# POWER.net
KiCad netlist of a schematic drawn in Altium Designer
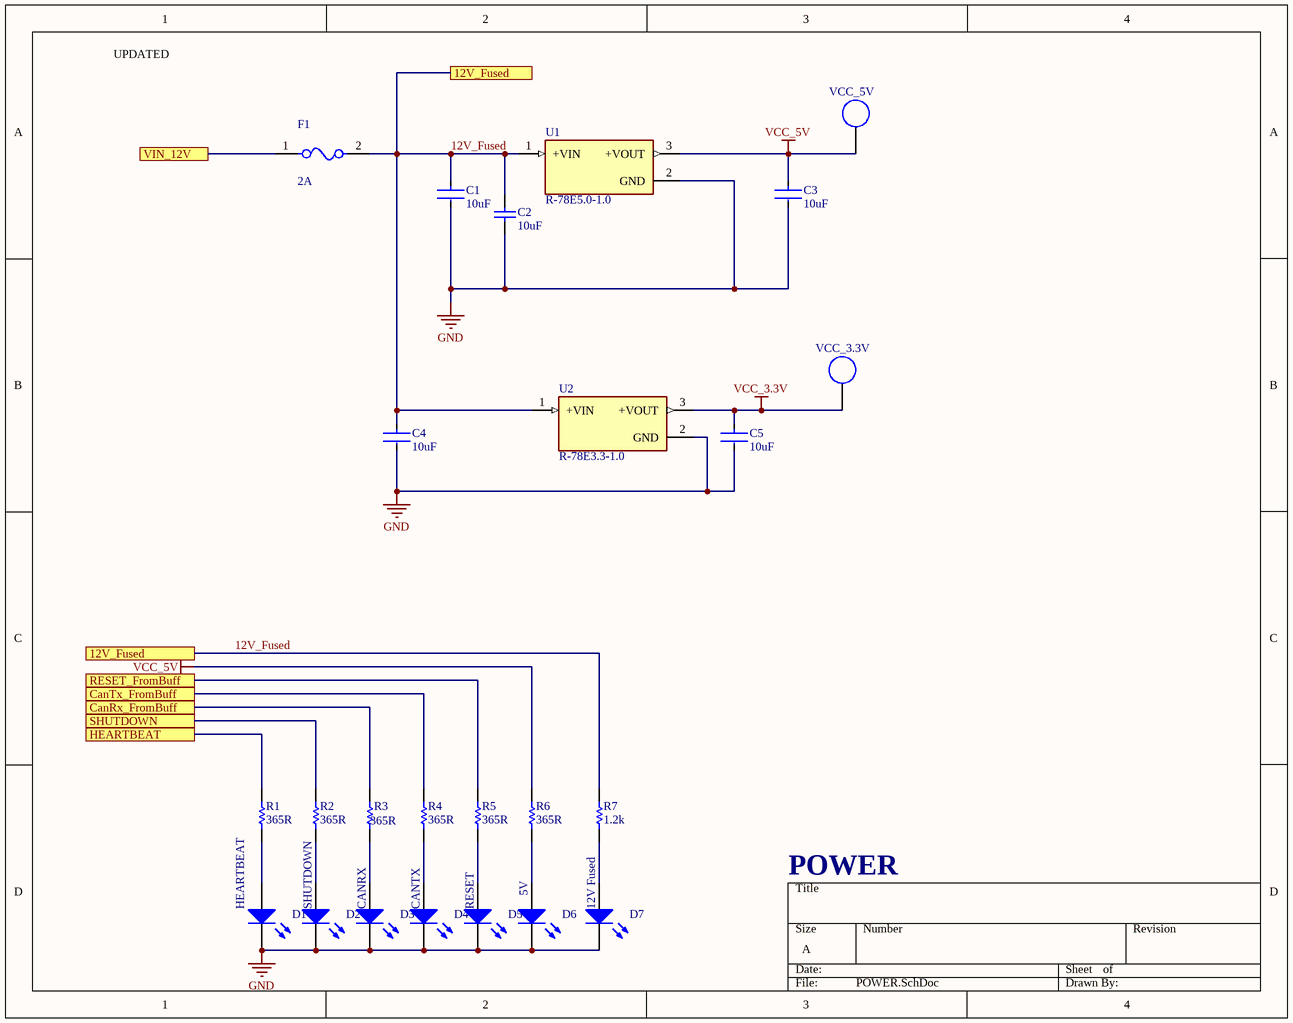
[diagram p0: POWER.SchDoc]

(export (version "E")
  (design (tool "Eeschema 10.0.6"))
  (components
    (comp (ref "C1")
      (value "10uF")
      (footprint "FP-C2012-125-0_2-MFG")
      (description "Multilayer Ceramic Capacitors 10μF ±10% 16V X6S SMD 0805")
      (fields (field (name "TOLERANCE") "10%"))
      (libsource (lib "Altium Content Vault") (part "b4654b650e69147ec39a6b967a45e02"))
    )
    (comp (ref "C2")
      (value "10uF")
      (footprint "CAPPRD200W50D550H1250")
      (description "Cap Alum 10UF 20% 25V Radial")
      (fields (field (name "PUBLISHER") "T.Tallo"))
      (libsource (lib "Passives") (part "Cap, TH, Electrolytic_5mm"))
    )
    (comp (ref "C3")
      (value "10uF")
      (footprint "FP-C2012-125-0_2-MFG")
      (description "Multilayer Ceramic Capacitors 10μF ±10% 16V X6S SMD 0805")
      (fields (field (name "TOLERANCE") "10%"))
      (libsource (lib "Altium Content Vault") (part "b4654b650e69147ec39a6b967a45e02"))
    )
    (comp (ref "C4")
      (value "10uF")
      (footprint "FP-C2012-125-0_2-MFG")
      (description "Multilayer Ceramic Capacitors 10μF ±10% 16V X6S SMD 0805")
      (fields (field (name "TOLERANCE") "10%"))
      (libsource (lib "Altium Content Vault") (part "b4654b650e69147ec39a6b967a45e02"))
    )
    (comp (ref "C5")
      (value "10uF")
      (footprint "FP-C2012-125-0_2-MFG")
      (description "Multilayer Ceramic Capacitors 10μF ±10% 16V X6S SMD 0805")
      (fields (field (name "TOLERANCE") "10%"))
      (libsource (lib "Altium Content Vault") (part "b4654b650e69147ec39a6b967a45e02"))
    )
    (comp (ref "D1")
      (value "HEARTBEAT")
      (footprint "0805_A")
      (description "SMD mono-color Chip LED, WL-SMCW, Bright Green")
      (fields (field (name "PARTNUMBER") "150080VS75000") (field (name "MANUFACTURER") "Wuerth Elektronik"))
      (libsource (lib "Altium Content Vault") (part "WE-LED_K1A2-2"))
    )
    (comp (ref "D2")
      (value "SHUTDOWN")
      (footprint "0805_A")
      (description "SMD mono-color Chip LED, WL-SMCW, Bright Green")
      (fields (field (name "PARTNUMBER") "150080VS75000") (field (name "MANUFACTURER") "Wuerth Elektronik"))
      (libsource (lib "Altium Content Vault") (part "WE-LED_K1A2-2"))
    )
    (comp (ref "D3")
      (value "CANRX")
      (footprint "0805_A")
      (description "SMD mono-color Chip LED, WL-SMCW, Bright Green")
      (fields (field (name "PARTNUMBER") "150080VS75000") (field (name "MANUFACTURER") "Wuerth Elektronik"))
      (libsource (lib "Altium Content Vault") (part "WE-LED_K1A2-2"))
    )
    (comp (ref "D4")
      (value "CANTX")
      (footprint "0805_A")
      (description "SMD mono-color Chip LED, WL-SMCW, Bright Green")
      (fields (field (name "PARTNUMBER") "150080VS75000") (field (name "MANUFACTURER") "Wuerth Elektronik"))
      (libsource (lib "Altium Content Vault") (part "WE-LED_K1A2-2"))
    )
    (comp (ref "D5")
      (value "RESET")
      (footprint "0805_A")
      (description "SMD mono-color Chip LED, WL-SMCW, Bright Green")
      (fields (field (name "PARTNUMBER") "150080VS75000") (field (name "MANUFACTURER") "Wuerth Elektronik"))
      (libsource (lib "Altium Content Vault") (part "WE-LED_K1A2-2"))
    )
    (comp (ref "D6")
      (value "5V")
      (footprint "0805_A")
      (description "SMD mono-color Chip LED, WL-SMCW, Bright Green")
      (fields (field (name "PARTNUMBER") "150080VS75000") (field (name "MANUFACTURER") "Wuerth Elektronik"))
      (libsource (lib "Altium Content Vault") (part "WE-LED_K1A2-2"))
    )
    (comp (ref "D7")
      (value "12V Fused")
      (footprint "0805_A")
      (description "SMD mono-color Chip LED, WL-SMCW, Bright Green")
      (fields (field (name "PARTNUMBER") "150080VS75000") (field (name "MANUFACTURER") "Wuerth Elektronik"))
      (libsource (lib "Altium Content Vault") (part "WE-LED_K1A2-2"))
    )
    (comp (ref "F1")
      (value "2A")
      (footprint "FP-0154-MFG")
      (description "FUSE BOARD MNT 2A 125VAC/VDC SMD")
      (fields
        (field (name "OCTOPART") "https://octopart.com/0154002.dr-littelfuse-565858")
        (field (name "MANUFACTURER PART NUMBER") "0154002.DR")
      )
      (libsource (lib "Altium Content Vault") (part "5bcf9b9f640e542cf0359d10258e979"))
    )
    (comp (ref "R1")
      (value "365R")
      (footprint "RESC2013X60X35ML10T20")
      (fields (field (name "PART NUMBER") "RC0805FR-07365RL") (field (name "MANUFACTURER") "Yageo"))
      (libsource (lib "Altium Content Vault") (part "RES"))
    )
    (comp (ref "R2")
      (value "365R")
      (footprint "RESC2013X60X35ML10T20")
      (fields (field (name "PART NUMBER") "RC0805FR-07365RL") (field (name "MANUFACTURER") "Yageo"))
      (libsource (lib "Altium Content Vault") (part "RES"))
    )
    (comp (ref "R3")
      (value "365R")
      (footprint "RESC2013X60X35ML10T20")
      (fields (field (name "PART NUMBER") "RC0805FR-07365RL") (field (name "MANUFACTURER") "Yageo"))
      (libsource (lib "Altium Content Vault") (part "RES"))
    )
    (comp (ref "R4")
      (value "365R")
      (footprint "RESC2013X60X35ML10T20")
      (fields (field (name "PART NUMBER") "RC0805FR-07365RL") (field (name "MANUFACTURER") "Yageo"))
      (libsource (lib "Altium Content Vault") (part "RES"))
    )
    (comp (ref "R5")
      (value "365R")
      (footprint "RESC2013X60X35ML10T20")
      (fields (field (name "PART NUMBER") "RC0805FR-07365RL") (field (name "MANUFACTURER") "Yageo"))
      (libsource (lib "Altium Content Vault") (part "RES"))
    )
    (comp (ref "R6")
      (value "365R")
      (footprint "RESC2013X60X35ML10T20")
      (fields (field (name "PART NUMBER") "RC0805FR-07365RL") (field (name "MANUFACTURER") "Yageo"))
      (libsource (lib "Altium Content Vault") (part "RES"))
    )
    (comp (ref "R7")
      (value "1.2k")
      (footprint "RESC2013X60X35ML10T20")
      (fields (field (name "PART NUMBER") "RC0805FR-071K24L") (field (name "MANUFACTURER") "Yageo"))
      (libsource (lib "Altium Content Vault") (part "RES"))
    )
    (comp (ref "U1")
      (value "R-78E5.0-1.0")
      (footprint "CONV_R-78E5.0-1.0")
      (description "1A DC/DC-Converter 'INNOLINE' SIP3 reg")
      (fields (field (name "MF") "Recom Power"))
      (libsource (lib "BMS_MasterboardUpdated_1") (part "R-78E5.0-1.0"))
    )
    (comp (ref "U2")
      (value "R-78E3.3-1.0")
      (footprint "CONV_R-78E3.3-1.0")
      (description "1A DC/DC-Converter 'INNOLINE' SIP3 reg")
      (fields (field (name "MF") "Recom Power") (field (name "DIGI-KEY_PART_NUMBER") "945-2409-5-ND"))
      (libsource (lib "BMS_MasterboardUpdated_1") (part "R-78E3.3-1.0"))
    )
    (comp (ref "VCC_3.3V")
      (value "5015")
      (footprint "5015")
      (description "SMD Test Point")
      (fields (field (name "MANUFACTURER") "Keystone Electronics") (field (name "PUBLISHER") "T.Tallo"))
      (libsource (lib "Connectors") (part "5015"))
    )
    (comp (ref "VCC_5V")
      (value "5015")
      (footprint "5015")
      (description "SMD Test Point")
      (fields (field (name "MANUFACTURER") "Keystone Electronics") (field (name "PUBLISHER") "T.Tallo"))
      (libsource (lib "Connectors") (part "5015"))
    )
  )
  (nets
    (net (code "1") (name "/12V_Fused") (class "Default")
      (node (ref "C1") (pin "1") (pinfunction "1_1") (pintype "passive"))
      (node (ref "C2") (pin "1") (pinfunction "Pos_1") (pintype "passive"))
      (node (ref "C4") (pin "1") (pinfunction "1_1") (pintype "passive"))
      (node (ref "F1") (pin "2") (pinfunction "2_2") (pintype "passive"))
      (node (ref "R7") (pin "2") (pinfunction "2_2") (pintype "passive"))
      (node (ref "U1") (pin "1") (pinfunction "+VIN_1") (pintype "input"))
      (node (ref "U2") (pin "1") (pinfunction "+VIN_1") (pintype "input"))
    )
    (net (code "2") (name "/CanRx_FromBuff") (class "Default")
      (node (ref "R3") (pin "2") (pinfunction "2_2") (pintype "passive"))
    )
    (net (code "3") (name "/CanTx_FromBuff") (class "Default")
      (node (ref "R4") (pin "2") (pinfunction "2_2") (pintype "passive"))
    )
    (net (code "4") (name "/HEARTBEAT") (class "Default")
      (node (ref "R1") (pin "2") (pinfunction "2_2") (pintype "passive"))
    )
    (net (code "5") (name "/RESET_FromBuff") (class "Default")
      (node (ref "R5") (pin "2") (pinfunction "2_2") (pintype "passive"))
    )
    (net (code "6") (name "/SHUTDOWN") (class "Default")
      (node (ref "R2") (pin "2") (pinfunction "2_2") (pintype "passive"))
    )
    (net (code "7") (name "/VIN_12V") (class "Default")
      (node (ref "F1") (pin "1") (pinfunction "1_1") (pintype "passive"))
    )
    (net (code "8") (name "GND") (class "Default")
      (node (ref "C1") (pin "2") (pinfunction "2_2") (pintype "passive"))
      (node (ref "C2") (pin "2") (pinfunction "Neg_2") (pintype "passive"))
      (node (ref "C3") (pin "2") (pinfunction "2_2") (pintype "passive"))
      (node (ref "C4") (pin "2") (pinfunction "2_2") (pintype "passive"))
      (node (ref "C5") (pin "2") (pinfunction "2_2") (pintype "passive"))
      (node (ref "D1") (pin "1") (pinfunction "K_1") (pintype "passive"))
      (node (ref "D2") (pin "1") (pinfunction "K_1") (pintype "passive"))
      (node (ref "D3") (pin "1") (pinfunction "K_1") (pintype "passive"))
      (node (ref "D4") (pin "1") (pinfunction "K_1") (pintype "passive"))
      (node (ref "D5") (pin "1") (pinfunction "K_1") (pintype "passive"))
      (node (ref "D6") (pin "1") (pinfunction "K_1") (pintype "passive"))
      (node (ref "D7") (pin "1") (pinfunction "K_1") (pintype "passive"))
      (node (ref "U1") (pin "2") (pinfunction "GND_2") (pintype "power_in"))
      (node (ref "U2") (pin "2") (pinfunction "GND_2") (pintype "power_in"))
    )
    (net (code "9") (name "Net-(D1-A)") (class "Default")
      (node (ref "D1") (pin "2") (pinfunction "A_2") (pintype "passive"))
      (node (ref "R1") (pin "1") (pinfunction "1_1") (pintype "passive"))
    )
    (net (code "10") (name "Net-(D2-A)") (class "Default")
      (node (ref "D2") (pin "2") (pinfunction "A_2") (pintype "passive"))
      (node (ref "R2") (pin "1") (pinfunction "1_1") (pintype "passive"))
    )
    (net (code "11") (name "Net-(D3-A)") (class "Default")
      (node (ref "D3") (pin "2") (pinfunction "A_2") (pintype "passive"))
      (node (ref "R3") (pin "1") (pinfunction "1_1") (pintype "passive"))
    )
    (net (code "12") (name "Net-(D4-A)") (class "Default")
      (node (ref "D4") (pin "2") (pinfunction "A_2") (pintype "passive"))
      (node (ref "R4") (pin "1") (pinfunction "1_1") (pintype "passive"))
    )
    (net (code "13") (name "Net-(D5-A)") (class "Default")
      (node (ref "D5") (pin "2") (pinfunction "A_2") (pintype "passive"))
      (node (ref "R5") (pin "1") (pinfunction "1_1") (pintype "passive"))
    )
    (net (code "14") (name "Net-(D6-A)") (class "Default")
      (node (ref "D6") (pin "2") (pinfunction "A_2") (pintype "passive"))
      (node (ref "R6") (pin "1") (pinfunction "1_1") (pintype "passive"))
    )
    (net (code "15") (name "Net-(D7-A)") (class "Default")
      (node (ref "D7") (pin "2") (pinfunction "A_2") (pintype "passive"))
      (node (ref "R7") (pin "1") (pinfunction "1_1") (pintype "passive"))
    )
    (net (code "16") (name "VCC_3.3V") (class "Default")
      (node (ref "C5") (pin "1") (pinfunction "1_1") (pintype "passive"))
      (node (ref "U2") (pin "3") (pinfunction "+VOUT_3") (pintype "output"))
      (node (ref "VCC_3.3V") (pin "1") (pinfunction "1_1") (pintype "passive"))
    )
    (net (code "17") (name "VCC_5V") (class "Default")
      (node (ref "C3") (pin "1") (pinfunction "1_1") (pintype "passive"))
      (node (ref "R6") (pin "2") (pinfunction "2_2") (pintype "passive"))
      (node (ref "U1") (pin "3") (pinfunction "+VOUT_3") (pintype "output"))
      (node (ref "VCC_5V") (pin "1") (pinfunction "1_1") (pintype "passive"))
    )
  )
)
